# v1_1_P.net
KiCad netlist of a schematic drawn in EAGLE
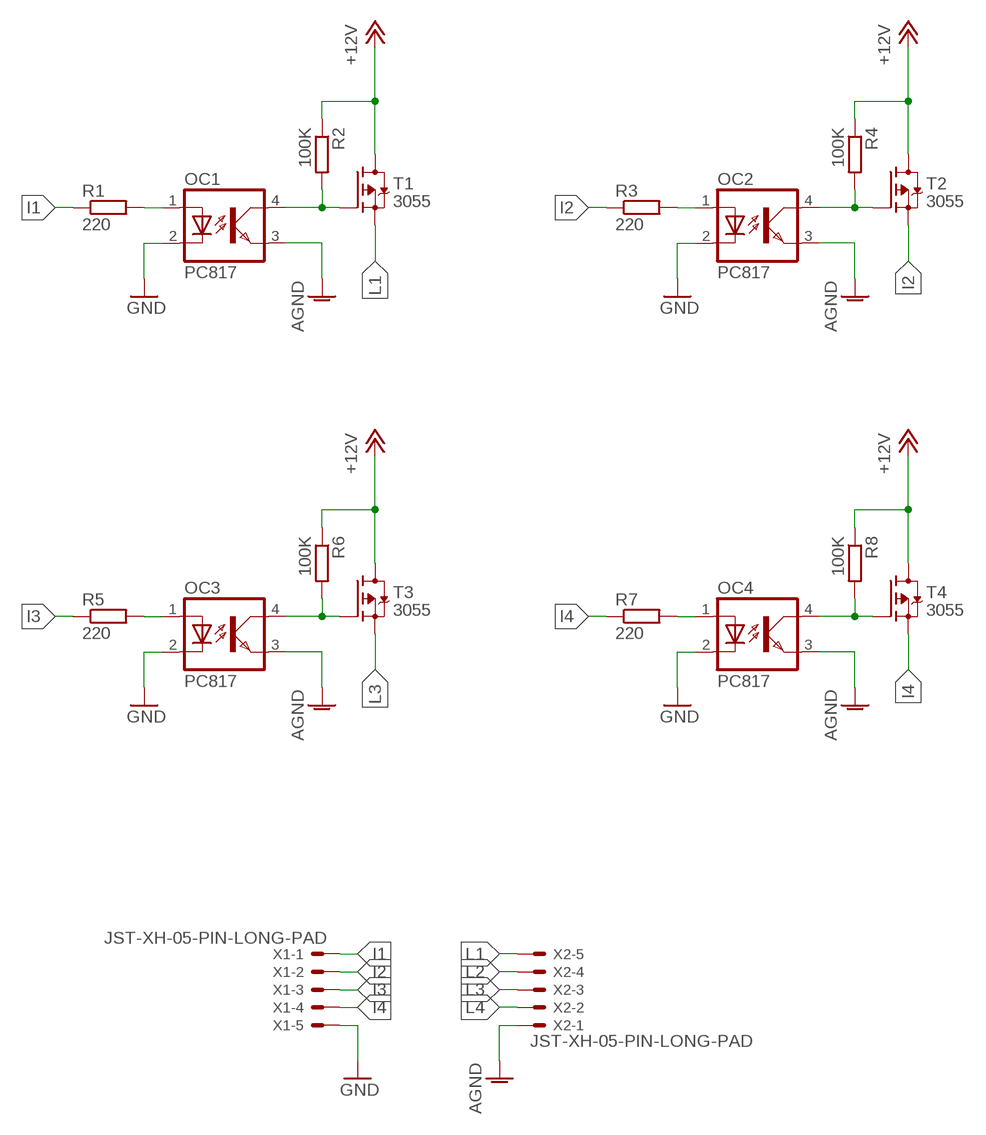
[diagram p0: schematic, sheet 1]

(export (version "E")
  (design (tool "Eeschema 10.0.6"))
  (components
    (comp (ref "OC1")
      (value "PC817")
      (footprint "eagle-import:DIL04")
      (libsource (lib "eagle-import") (part "PC817"))
    )
    (comp (ref "OC2")
      (value "PC817")
      (footprint "eagle-import:DIL04")
      (libsource (lib "eagle-import") (part "PC817"))
    )
    (comp (ref "OC3")
      (value "PC817")
      (footprint "eagle-import:DIL04")
      (libsource (lib "eagle-import") (part "PC817"))
    )
    (comp (ref "OC4")
      (value "PC817")
      (footprint "eagle-import:DIL04")
      (libsource (lib "eagle-import") (part "PC817"))
    )
    (comp (ref "R1")
      (value "220")
      (footprint "eagle-import:R0603")
      (libsource (lib "eagle-import") (part "R-EU_R0603"))
    )
    (comp (ref "R2")
      (value "100K")
      (footprint "eagle-import:R0603")
      (libsource (lib "eagle-import") (part "R-EU_R0603"))
    )
    (comp (ref "R3")
      (value "220")
      (footprint "eagle-import:R0603")
      (libsource (lib "eagle-import") (part "R-EU_R0603"))
    )
    (comp (ref "R4")
      (value "100K")
      (footprint "eagle-import:R0603")
      (libsource (lib "eagle-import") (part "R-EU_R0603"))
    )
    (comp (ref "R5")
      (value "220")
      (footprint "eagle-import:R0603")
      (libsource (lib "eagle-import") (part "R-EU_R0603"))
    )
    (comp (ref "R6")
      (value "100K")
      (footprint "eagle-import:R0603")
      (libsource (lib "eagle-import") (part "R-EU_R0603"))
    )
    (comp (ref "R7")
      (value "220")
      (footprint "eagle-import:R0603")
      (libsource (lib "eagle-import") (part "R-EU_R0603"))
    )
    (comp (ref "R8")
      (value "100K")
      (footprint "eagle-import:R0603")
      (libsource (lib "eagle-import") (part "R-EU_R0603"))
    )
    (comp (ref "T1")
      (value "3055")
      (footprint "eagle-import:MOSFET_P_SOT223")
      (libsource (lib "eagle-import") (part "MOSFET_P_SOT223"))
    )
    (comp (ref "T2")
      (value "3055")
      (footprint "eagle-import:MOSFET_P_SOT223")
      (libsource (lib "eagle-import") (part "MOSFET_P_SOT223"))
    )
    (comp (ref "T3")
      (value "3055")
      (footprint "eagle-import:MOSFET_P_SOT223")
      (libsource (lib "eagle-import") (part "MOSFET_P_SOT223"))
    )
    (comp (ref "T4")
      (value "3055")
      (footprint "eagle-import:MOSFET_P_SOT223")
      (libsource (lib "eagle-import") (part "MOSFET_P_SOT223"))
    )
    (comp (ref "X1")
      (value "JST-XH-05-PIN-LONG-PAD")
      (footprint "eagle-import:JST-XH-05-PACKAGE-LONG-PAD")
      (libsource (lib "eagle-import") (part "JST-XH-05-PIN-LONG-PAD"))
    )
    (comp (ref "X2")
      (value "JST-XH-05-PIN-LONG-PAD")
      (footprint "eagle-import:JST-XH-05-PACKAGE-LONG-PAD")
      (libsource (lib "eagle-import") (part "JST-XH-05-PIN-LONG-PAD"))
    )
  )
  (nets
    (net (code "1") (name "+12V") (class "Default")
      (node (ref "R2") (pin "1") (pinfunction "1_1") (pintype "passive"))
      (node (ref "R4") (pin "1") (pinfunction "1_1") (pintype "passive"))
      (node (ref "R6") (pin "1") (pinfunction "1_1") (pintype "passive"))
      (node (ref "R8") (pin "1") (pinfunction "1_1") (pintype "passive"))
      (node (ref "T1") (pin "2") (pinfunction "D_2") (pintype "passive"))
      (node (ref "T1") (pin "4") (pinfunction "D_4") (pintype "passive"))
      (node (ref "T2") (pin "2") (pinfunction "D_2") (pintype "passive"))
      (node (ref "T2") (pin "4") (pinfunction "D_4") (pintype "passive"))
      (node (ref "T3") (pin "2") (pinfunction "D_2") (pintype "passive"))
      (node (ref "T3") (pin "4") (pinfunction "D_4") (pintype "passive"))
      (node (ref "T4") (pin "2") (pinfunction "D_2") (pintype "passive"))
      (node (ref "T4") (pin "4") (pinfunction "D_4") (pintype "passive"))
    )
    (net (code "2") (name "AGND") (class "Default")
      (node (ref "OC1") (pin "3") (pinfunction "EMIT_3") (pintype "passive"))
      (node (ref "OC2") (pin "3") (pinfunction "EMIT_3") (pintype "passive"))
      (node (ref "OC3") (pin "3") (pinfunction "EMIT_3") (pintype "passive"))
      (node (ref "OC4") (pin "3") (pinfunction "EMIT_3") (pintype "passive"))
      (node (ref "X2") (pin "1") (pinfunction "S_1") (pintype "passive"))
    )
    (net (code "3") (name "GND") (class "Default")
      (node (ref "OC1") (pin "2") (pinfunction "C_2") (pintype "passive"))
      (node (ref "OC2") (pin "2") (pinfunction "C_2") (pintype "passive"))
      (node (ref "OC3") (pin "2") (pinfunction "C_2") (pintype "passive"))
      (node (ref "OC4") (pin "2") (pinfunction "C_2") (pintype "passive"))
      (node (ref "X1") (pin "5") (pinfunction "S_5") (pintype "passive"))
    )
    (net (code "4") (name "I1") (class "Default")
      (node (ref "R1") (pin "1") (pinfunction "1_1") (pintype "passive"))
      (node (ref "X1") (pin "1") (pinfunction "S_1") (pintype "passive"))
    )
    (net (code "5") (name "I2") (class "Default")
      (node (ref "R3") (pin "1") (pinfunction "1_1") (pintype "passive"))
      (node (ref "T2") (pin "3") (pinfunction "S_3") (pintype "passive"))
      (node (ref "X1") (pin "2") (pinfunction "S_2") (pintype "passive"))
    )
    (net (code "6") (name "I3") (class "Default")
      (node (ref "R5") (pin "1") (pinfunction "1_1") (pintype "passive"))
      (node (ref "X1") (pin "3") (pinfunction "S_3") (pintype "passive"))
    )
    (net (code "7") (name "I4") (class "Default")
      (node (ref "R7") (pin "1") (pinfunction "1_1") (pintype "passive"))
      (node (ref "T4") (pin "3") (pinfunction "S_3") (pintype "passive"))
      (node (ref "X1") (pin "4") (pinfunction "S_4") (pintype "passive"))
    )
    (net (code "8") (name "L1") (class "Default")
      (node (ref "T1") (pin "3") (pinfunction "S_3") (pintype "passive"))
      (node (ref "X2") (pin "5") (pinfunction "S_5") (pintype "passive"))
    )
    (net (code "9") (name "L2") (class "Default")
      (node (ref "X2") (pin "4") (pinfunction "S_4") (pintype "passive"))
    )
    (net (code "10") (name "L3") (class "Default")
      (node (ref "T3") (pin "3") (pinfunction "S_3") (pintype "passive"))
      (node (ref "X2") (pin "3") (pinfunction "S_3") (pintype "passive"))
    )
    (net (code "11") (name "L4") (class "Default")
      (node (ref "X2") (pin "2") (pinfunction "S_2") (pintype "passive"))
    )
    (net (code "12") (name "Net-(OC1-A)") (class "Default")
      (node (ref "OC1") (pin "1") (pinfunction "A_1") (pintype "passive"))
      (node (ref "R1") (pin "2") (pinfunction "2_2") (pintype "passive"))
    )
    (net (code "13") (name "Net-(OC1-COL)") (class "Default")
      (node (ref "OC1") (pin "4") (pinfunction "COL_4") (pintype "passive"))
      (node (ref "R2") (pin "2") (pinfunction "2_2") (pintype "passive"))
      (node (ref "T1") (pin "1") (pinfunction "G_1") (pintype "passive"))
    )
    (net (code "14") (name "Net-(OC2-A)") (class "Default")
      (node (ref "OC2") (pin "1") (pinfunction "A_1") (pintype "passive"))
      (node (ref "R3") (pin "2") (pinfunction "2_2") (pintype "passive"))
    )
    (net (code "15") (name "Net-(OC2-COL)") (class "Default")
      (node (ref "OC2") (pin "4") (pinfunction "COL_4") (pintype "passive"))
      (node (ref "R4") (pin "2") (pinfunction "2_2") (pintype "passive"))
      (node (ref "T2") (pin "1") (pinfunction "G_1") (pintype "passive"))
    )
    (net (code "16") (name "Net-(OC3-A)") (class "Default")
      (node (ref "OC3") (pin "1") (pinfunction "A_1") (pintype "passive"))
      (node (ref "R5") (pin "2") (pinfunction "2_2") (pintype "passive"))
    )
    (net (code "17") (name "Net-(OC3-COL)") (class "Default")
      (node (ref "OC3") (pin "4") (pinfunction "COL_4") (pintype "passive"))
      (node (ref "R6") (pin "2") (pinfunction "2_2") (pintype "passive"))
      (node (ref "T3") (pin "1") (pinfunction "G_1") (pintype "passive"))
    )
    (net (code "18") (name "Net-(OC4-A)") (class "Default")
      (node (ref "OC4") (pin "1") (pinfunction "A_1") (pintype "passive"))
      (node (ref "R7") (pin "2") (pinfunction "2_2") (pintype "passive"))
    )
    (net (code "19") (name "Net-(OC4-COL)") (class "Default")
      (node (ref "OC4") (pin "4") (pinfunction "COL_4") (pintype "passive"))
      (node (ref "R8") (pin "2") (pinfunction "2_2") (pintype "passive"))
      (node (ref "T4") (pin "1") (pinfunction "G_1") (pintype "passive"))
    )
  )
)
